# Day0_-_Rhenetou_Virginio_-13215022.net
KiCad netlist of a schematic drawn in EAGLE
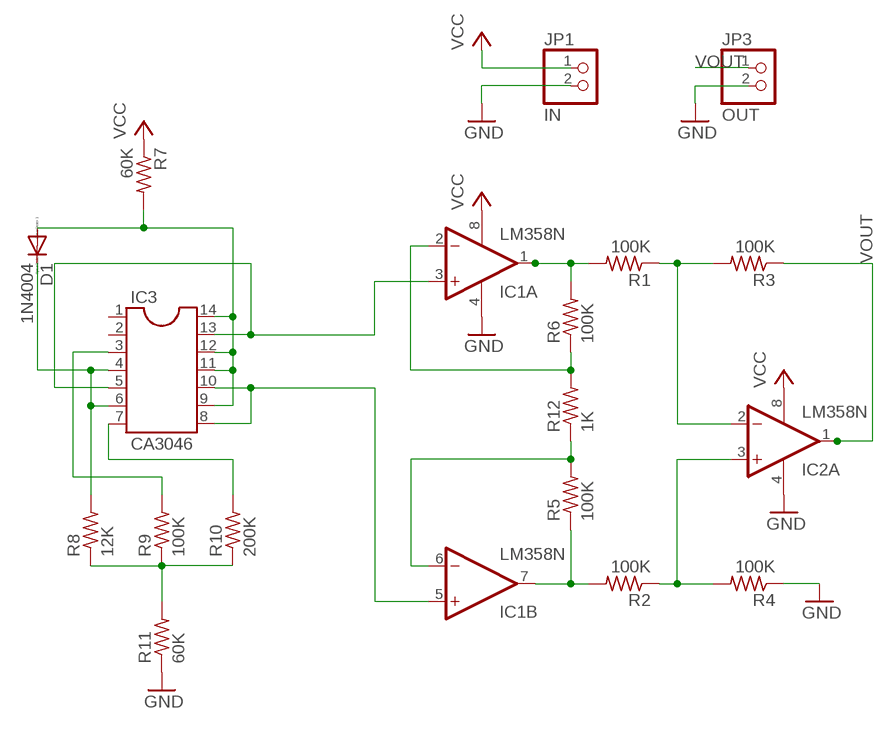
[diagram p0: schematic, sheet 1]

(export (version "E")
  (design (tool "Eeschema 10.0.6"))
  (components
    (comp (ref "D1")
      (value "1N4004")
      (footprint "eagle-import:D-7.5")
      (libsource (lib "eagle-import") (part "DIODE-D-7.5"))
    )
    (comp (ref "IC1")
      (value "LM358N")
      (footprint "eagle-import:DIL08")
      (libsource (lib "eagle-import") (part "LM358N"))
    )
    (comp (ref "IC2")
      (value "LM358N")
      (footprint "eagle-import:DIL08")
      (libsource (lib "eagle-import") (part "LM358N"))
    )
    (comp (ref "IC3")
      (value "CA3046")
      (footprint "eagle-import:DIL14")
      (libsource (lib "eagle-import") (part "DIL14"))
    )
    (comp (ref "JP1")
      (value "IN")
      (footprint "eagle-import:1X02")
      (libsource (lib "eagle-import") (part "PINHD-1X2"))
    )
    (comp (ref "JP3")
      (value "OUT")
      (footprint "eagle-import:1X02")
      (libsource (lib "eagle-import") (part "PINHD-1X2"))
    )
    (comp (ref "R1")
      (value "100K")
      (footprint "eagle-import:0204_7")
      (libsource (lib "eagle-import") (part "R-US_0204/7"))
    )
    (comp (ref "R2")
      (value "100K")
      (footprint "eagle-import:0204_7")
      (libsource (lib "eagle-import") (part "R-US_0204/7"))
    )
    (comp (ref "R3")
      (value "100K")
      (footprint "eagle-import:0204_7")
      (libsource (lib "eagle-import") (part "R-US_0204/7"))
    )
    (comp (ref "R4")
      (value "100K")
      (footprint "eagle-import:0204_7")
      (libsource (lib "eagle-import") (part "R-US_0204/7"))
    )
    (comp (ref "R5")
      (value "100K")
      (footprint "eagle-import:0204_7")
      (libsource (lib "eagle-import") (part "R-US_0204/7"))
    )
    (comp (ref "R6")
      (value "100K")
      (footprint "eagle-import:0204_7")
      (libsource (lib "eagle-import") (part "R-US_0204/7"))
    )
    (comp (ref "R7")
      (value "60K")
      (footprint "eagle-import:0204_7")
      (libsource (lib "eagle-import") (part "R-US_0204/7"))
    )
    (comp (ref "R8")
      (value "12K")
      (footprint "eagle-import:0204_7")
      (libsource (lib "eagle-import") (part "R-US_0204/7"))
    )
    (comp (ref "R9")
      (value "100K")
      (footprint "eagle-import:0204_7")
      (libsource (lib "eagle-import") (part "R-US_0204/7"))
    )
    (comp (ref "R10")
      (value "200K")
      (footprint "eagle-import:0204_7")
      (libsource (lib "eagle-import") (part "R-US_0204/7"))
    )
    (comp (ref "R11")
      (value "60K")
      (footprint "eagle-import:0204_7")
      (libsource (lib "eagle-import") (part "R-US_0204/7"))
    )
    (comp (ref "R12")
      (value "1K")
      (footprint "eagle-import:0204_7")
      (libsource (lib "eagle-import") (part "R-US_0204/7"))
    )
  )
  (nets
    (net (code "1") (name "/VOUT") (class "Default")
      (node (ref "IC2") (pin "1") (pinfunction "OUT_1") (pintype "output"))
      (node (ref "JP3") (pin "1") (pinfunction "1_1") (pintype "passive"))
      (node (ref "R3") (pin "1") (pinfunction "1_1") (pintype "passive"))
    )
    (net (code "2") (name "GND") (class "Default")
      (node (ref "IC1") (pin "4") (pinfunction "V-_4") (pintype "power_in"))
      (node (ref "IC2") (pin "4") (pinfunction "V-_4") (pintype "power_in"))
      (node (ref "JP1") (pin "2") (pinfunction "2_2") (pintype "passive"))
      (node (ref "JP3") (pin "2") (pinfunction "2_2") (pintype "passive"))
      (node (ref "R11") (pin "1") (pinfunction "1_1") (pintype "passive"))
      (node (ref "R4") (pin "1") (pinfunction "1_1") (pintype "passive"))
    )
    (net (code "3") (name "Net-(D1-PadA)") (class "Default")
      (node (ref "D1") (pin "A") (pinfunction "A_A") (pintype "passive"))
      (node (ref "IC3") (pin "11") (pinfunction "11_11") (pintype "passive"))
      (node (ref "IC3") (pin "12") (pinfunction "12_12") (pintype "passive"))
      (node (ref "IC3") (pin "14") (pinfunction "14_14") (pintype "passive"))
      (node (ref "IC3") (pin "9") (pinfunction "9_9") (pintype "passive"))
      (node (ref "R7") (pin "2") (pinfunction "2_2") (pintype "passive"))
    )
    (net (code "4") (name "Net-(D1-PadC)") (class "Default")
      (node (ref "D1") (pin "C") (pinfunction "C_C") (pintype "passive"))
      (node (ref "IC3") (pin "4") (pinfunction "4_4") (pintype "passive"))
      (node (ref "IC3") (pin "6") (pinfunction "6_6") (pintype "passive"))
      (node (ref "R8") (pin "2") (pinfunction "2_2") (pintype "passive"))
    )
    (net (code "5") (name "Net-(IC1A-+IN)") (class "Default")
      (node (ref "IC1") (pin "3") (pinfunction "+IN_3") (pintype "input"))
      (node (ref "IC3") (pin "13") (pinfunction "13_13") (pintype "passive"))
      (node (ref "IC3") (pin "5") (pinfunction "5_5") (pintype "passive"))
    )
    (net (code "6") (name "Net-(IC1A--IN)") (class "Default")
      (node (ref "IC1") (pin "2") (pinfunction "-IN_2") (pintype "input"))
      (node (ref "R12") (pin "2") (pinfunction "2_2") (pintype "passive"))
      (node (ref "R6") (pin "1") (pinfunction "1_1") (pintype "passive"))
    )
    (net (code "7") (name "Net-(IC1A-OUT)") (class "Default")
      (node (ref "IC1") (pin "1") (pinfunction "OUT_1") (pintype "output"))
      (node (ref "R1") (pin "2") (pinfunction "2_2") (pintype "passive"))
      (node (ref "R6") (pin "2") (pinfunction "2_2") (pintype "passive"))
    )
    (net (code "8") (name "Net-(IC1B-+IN)") (class "Default")
      (node (ref "IC1") (pin "5") (pinfunction "+IN_5") (pintype "input"))
      (node (ref "IC3") (pin "10") (pinfunction "10_10") (pintype "passive"))
      (node (ref "IC3") (pin "8") (pinfunction "8_8") (pintype "passive"))
    )
    (net (code "9") (name "Net-(IC1B--IN)") (class "Default")
      (node (ref "IC1") (pin "6") (pinfunction "-IN_6") (pintype "input"))
      (node (ref "R12") (pin "1") (pinfunction "1_1") (pintype "passive"))
      (node (ref "R5") (pin "2") (pinfunction "2_2") (pintype "passive"))
    )
    (net (code "10") (name "Net-(IC1B-OUT)") (class "Default")
      (node (ref "IC1") (pin "7") (pinfunction "OUT_7") (pintype "output"))
      (node (ref "R2") (pin "2") (pinfunction "2_2") (pintype "passive"))
      (node (ref "R5") (pin "1") (pinfunction "1_1") (pintype "passive"))
    )
    (net (code "11") (name "Net-(IC2A-+IN)") (class "Default")
      (node (ref "IC2") (pin "3") (pinfunction "+IN_3") (pintype "input"))
      (node (ref "R2") (pin "1") (pinfunction "1_1") (pintype "passive"))
      (node (ref "R4") (pin "2") (pinfunction "2_2") (pintype "passive"))
    )
    (net (code "12") (name "Net-(IC2A--IN)") (class "Default")
      (node (ref "IC2") (pin "2") (pinfunction "-IN_2") (pintype "input"))
      (node (ref "R1") (pin "1") (pinfunction "1_1") (pintype "passive"))
      (node (ref "R3") (pin "2") (pinfunction "2_2") (pintype "passive"))
    )
    (net (code "13") (name "Net-(IC3-Pad3)") (class "Default")
      (node (ref "IC3") (pin "3") (pinfunction "3_3") (pintype "passive"))
      (node (ref "R9") (pin "2") (pinfunction "2_2") (pintype "passive"))
    )
    (net (code "14") (name "Net-(IC3-Pad7)") (class "Default")
      (node (ref "IC3") (pin "7") (pinfunction "7_7") (pintype "passive"))
      (node (ref "R10") (pin "2") (pinfunction "2_2") (pintype "passive"))
    )
    (net (code "15") (name "Net-(R10-Pad1)") (class "Default")
      (node (ref "R10") (pin "1") (pinfunction "1_1") (pintype "passive"))
      (node (ref "R11") (pin "2") (pinfunction "2_2") (pintype "passive"))
      (node (ref "R8") (pin "1") (pinfunction "1_1") (pintype "passive"))
      (node (ref "R9") (pin "1") (pinfunction "1_1") (pintype "passive"))
    )
    (net (code "16") (name "VCC") (class "Default")
      (node (ref "IC1") (pin "8") (pinfunction "V+_8") (pintype "power_in"))
      (node (ref "IC2") (pin "8") (pinfunction "V+_8") (pintype "power_in"))
      (node (ref "JP1") (pin "1") (pinfunction "1_1") (pintype "passive"))
      (node (ref "R7") (pin "1") (pinfunction "1_1") (pintype "passive"))
    )
    (net (code "17") (name "unconnected-(IC3-Pad1)") (class "Default")
      (node (ref "IC3") (pin "1") (pinfunction "1_1") (pintype "passive"))
    )
    (net (code "18") (name "unconnected-(IC3-Pad2)") (class "Default")
      (node (ref "IC3") (pin "2") (pinfunction "2_2") (pintype "passive"))
    )
  )
)
